# STC12C5A_DIP40_Mini.net
KiCad netlist of a schematic drawn in Altium Designer
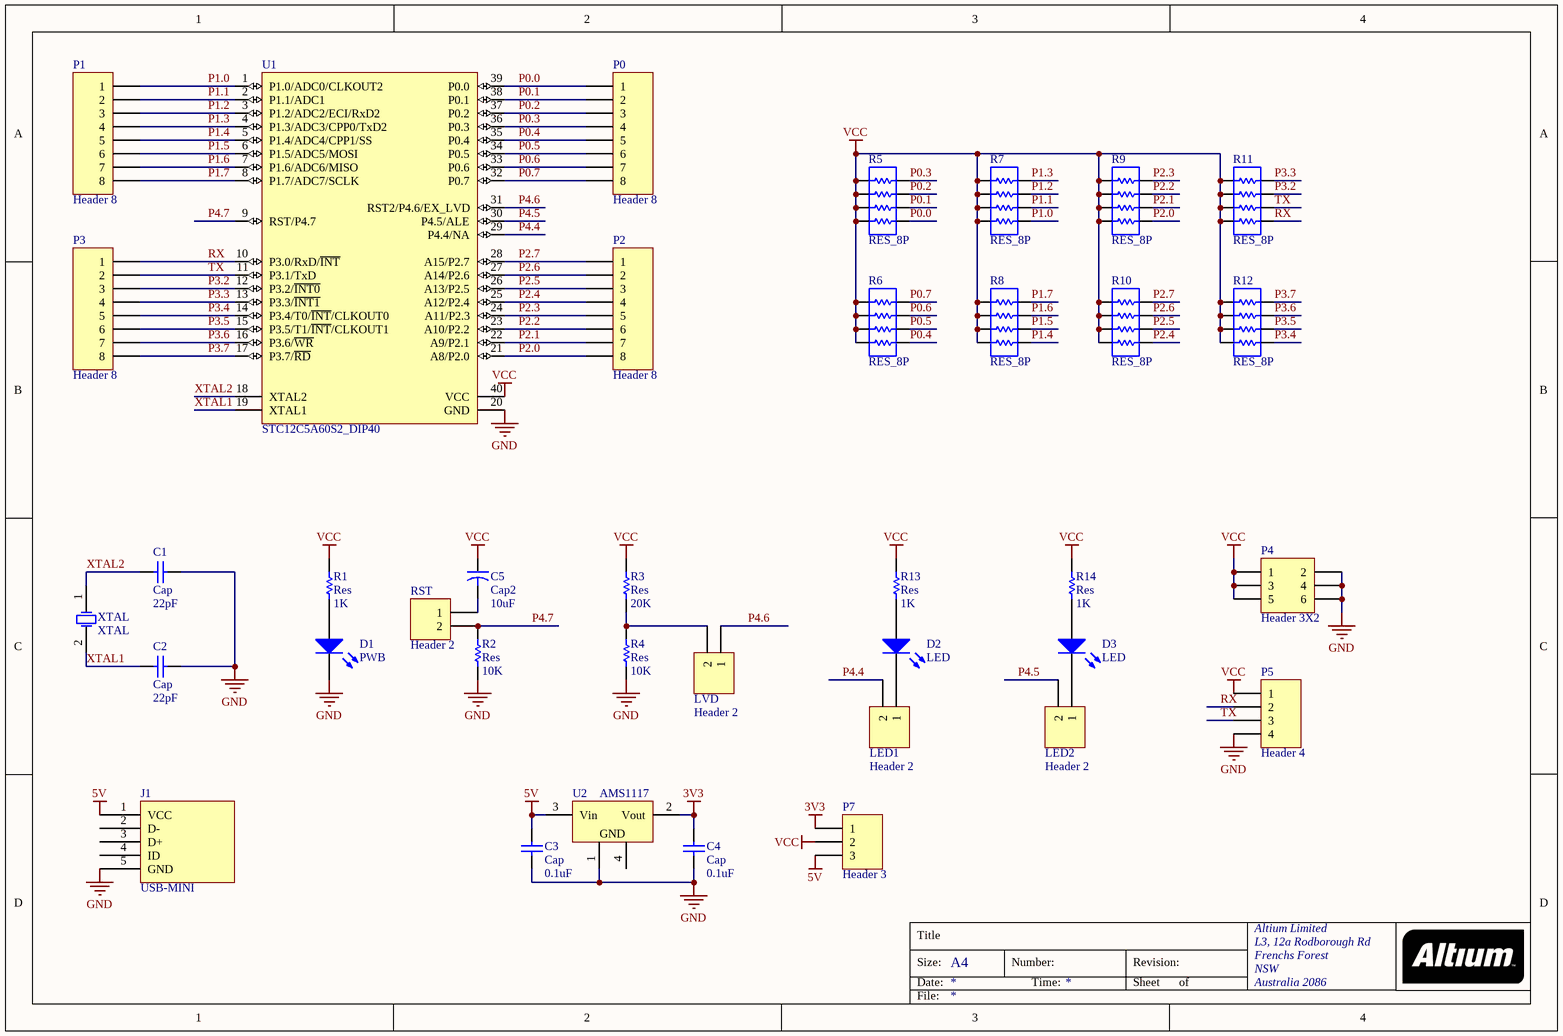
[diagram p0: STC12C5A_DIP40_Mini.SchDoc]

(export (version "E")
  (design (tool "Eeschema 10.0.6"))
  (components
    (comp (ref "C1")
      (value "Cap")
      (footprint "C0805")
      (description "Capacitor")
      (fields (field (name "ALTIUM_VALUE") "22pF") (field (name "PUBLISHER") "Altium Limited"))
      (libsource (lib "Devices") (part "Cap"))
    )
    (comp (ref "C2")
      (value "Cap")
      (footprint "C0805")
      (description "Capacitor")
      (fields (field (name "ALTIUM_VALUE") "22pF") (field (name "PUBLISHER") "Altium Limited"))
      (libsource (lib "Devices") (part "Cap"))
    )
    (comp (ref "C3")
      (value "Cap")
      (footprint "C0805")
      (description "Capacitor")
      (fields (field (name "ALTIUM_VALUE") "0.1uF") (field (name "PUBLISHER") "Altium Limited"))
      (libsource (lib "Devices") (part "Cap"))
    )
    (comp (ref "C4")
      (value "Cap")
      (footprint "C0805")
      (description "Capacitor")
      (fields (field (name "ALTIUM_VALUE") "0.1uF") (field (name "PUBLISHER") "Altium Limited"))
      (libsource (lib "Devices") (part "Cap"))
    )
    (comp (ref "C5")
      (value "Cap2")
      (footprint "C1210")
      (description "Capacitor")
      (fields (field (name "ALTIUM_VALUE") "10uF") (field (name "PUBLISHER") "Altium Limited"))
      (libsource (lib "Devices") (part "Cap2"))
    )
    (comp (ref "D1")
      (value "PWB")
      (footprint "C0805")
      (description "发光二极管")
      (libsource (lib "Devices") (part "LED-2P"))
    )
    (comp (ref "D2")
      (value "LED")
      (footprint "C0805")
      (description "发光二极管")
      (libsource (lib "Devices") (part "LED-2P"))
    )
    (comp (ref "D3")
      (value "LED")
      (footprint "C0805")
      (description "发光二极管")
      (libsource (lib "Devices") (part "LED-2P"))
    )
    (comp (ref "J1")
      (value "USB-MINI")
      (footprint "USB-MINI-B-SM")
      (libsource (lib "Connectors") (part "USB-MINI"))
    )
    (comp (ref "LED1")
      (value "Header 2")
      (footprint "HDR1X2")
      (description "Header, 2-Pin")
      (fields (field (name "PUBLISHER") "Altium Limited"))
      (libsource (lib "Connectors") (part "Header 2"))
    )
    (comp (ref "LED2")
      (value "Header 2")
      (footprint "HDR1X2")
      (description "Header, 2-Pin")
      (fields (field (name "PUBLISHER") "Altium Limited"))
      (libsource (lib "Connectors") (part "Header 2"))
    )
    (comp (ref "LVD")
      (value "Header 2")
      (footprint "HDR1X2")
      (description "Header, 2-Pin")
      (fields (field (name "PUBLISHER") "Altium Limited"))
      (libsource (lib "Connectors") (part "Header 2"))
    )
    (comp (ref "P0")
      (value "Header 8")
      (footprint "HDR1X8")
      (description "Header, 8-Pin")
      (fields (field (name "PUBLISHER") "Altium Limited"))
      (libsource (lib "Connectors") (part "Header 8"))
    )
    (comp (ref "P1")
      (value "Header 8")
      (footprint "HDR1X8")
      (description "Header, 8-Pin")
      (fields (field (name "PUBLISHER") "Altium Limited"))
      (libsource (lib "") (part "Header 8_1"))
    )
    (comp (ref "P2")
      (value "Header 8")
      (footprint "HDR1X8")
      (description "Header, 8-Pin")
      (fields (field (name "PUBLISHER") "Altium Limited"))
      (libsource (lib "Connectors") (part "Header 8"))
    )
    (comp (ref "P3")
      (value "Header 8")
      (footprint "HDR1X8")
      (description "Header, 8-Pin")
      (fields (field (name "PUBLISHER") "Altium Limited"))
      (libsource (lib "") (part "Header 8_1"))
    )
    (comp (ref "P4")
      (value "Header 3X2")
      (footprint "HDR2X3")
      (description "Header, 3-Pin, Dual row")
      (fields (field (name "PUBLISHER") "Altium Limited"))
      (libsource (lib "Connectors") (part "Header 3X2"))
    )
    (comp (ref "P5")
      (value "Header 4")
      (footprint "HDR1X4")
      (description "Header, 4-Pin")
      (fields (field (name "PUBLISHER") "Altium Limited"))
      (libsource (lib "Connectors") (part "Header 4"))
    )
    (comp (ref "P7")
      (value "Header 3")
      (footprint "HDR1X3")
      (description "Header, 3-Pin")
      (fields (field (name "PUBLISHER") "Altium Limited"))
      (libsource (lib "Connectors") (part "Header 3"))
    )
    (comp (ref "R1")
      (value "Res")
      (footprint "0805")
      (description "Resistor")
      (fields (field (name "ALTIUM_VALUE") "1K") (field (name "PUBLISHER") "Altium Limited"))
      (libsource (lib "Devices") (part "Res"))
    )
    (comp (ref "R2")
      (value "Res")
      (footprint "0805")
      (description "Resistor")
      (fields (field (name "ALTIUM_VALUE") "10K") (field (name "PUBLISHER") "Altium Limited"))
      (libsource (lib "Devices") (part "Res"))
    )
    (comp (ref "R3")
      (value "Res")
      (footprint "0805")
      (description "Resistor")
      (fields (field (name "ALTIUM_VALUE") "20K") (field (name "PUBLISHER") "Altium Limited"))
      (libsource (lib "Devices") (part "Res"))
    )
    (comp (ref "R4")
      (value "Res")
      (footprint "0805")
      (description "Resistor")
      (fields (field (name "ALTIUM_VALUE") "10K") (field (name "PUBLISHER") "Altium Limited"))
      (libsource (lib "Devices") (part "Res"))
    )
    (comp (ref "R5")
      (value "RES_8P")
      (footprint "RES_8P_0603")
      (description "贴片排阻")
      (libsource (lib "Devices") (part "RES_8P"))
    )
    (comp (ref "R6")
      (value "RES_8P")
      (footprint "RES_8P_0603")
      (description "贴片排阻")
      (libsource (lib "Devices") (part "RES_8P"))
    )
    (comp (ref "R7")
      (value "RES_8P")
      (footprint "RES_8P_0603")
      (description "贴片排阻")
      (libsource (lib "Devices") (part "RES_8P"))
    )
    (comp (ref "R8")
      (value "RES_8P")
      (footprint "RES_8P_0603")
      (description "贴片排阻")
      (libsource (lib "Devices") (part "RES_8P"))
    )
    (comp (ref "R9")
      (value "RES_8P")
      (footprint "RES_8P_0603")
      (description "贴片排阻")
      (libsource (lib "Devices") (part "RES_8P"))
    )
    (comp (ref "R10")
      (value "RES_8P")
      (footprint "RES_8P_0603")
      (description "贴片排阻")
      (libsource (lib "Devices") (part "RES_8P"))
    )
    (comp (ref "R11")
      (value "RES_8P")
      (footprint "RES_8P_0603")
      (description "贴片排阻")
      (libsource (lib "Devices") (part "RES_8P"))
    )
    (comp (ref "R12")
      (value "RES_8P")
      (footprint "RES_8P_0603")
      (description "贴片排阻")
      (libsource (lib "Devices") (part "RES_8P"))
    )
    (comp (ref "R13")
      (value "Res")
      (footprint "0805")
      (description "Resistor")
      (fields (field (name "ALTIUM_VALUE") "1K") (field (name "PUBLISHER") "Altium Limited"))
      (libsource (lib "Devices") (part "Res"))
    )
    (comp (ref "R14")
      (value "Res")
      (footprint "0805")
      (description "Resistor")
      (fields (field (name "ALTIUM_VALUE") "1K") (field (name "PUBLISHER") "Altium Limited"))
      (libsource (lib "Devices") (part "Res"))
    )
    (comp (ref "RST")
      (value "Header 2")
      (footprint "HDR1X2")
      (description "Header, 2-Pin")
      (fields (field (name "PUBLISHER") "Altium Limited"))
      (libsource (lib "Connectors") (part "Header 2"))
    )
    (comp (ref "U1")
      (value "STC12C5A60S2_DIP40")
      (footprint "DIP40")
      (description "增强型8051单片机")
      (libsource (lib "STC") (part "STC12C5A60S2_DIP40"))
    )
    (comp (ref "U2")
      (value "AMS1117")
      (footprint "SOT-223")
      (description "低压稳压器-1A")
      (libsource (lib "IC") (part "AMS1117"))
    )
    (comp (ref "XTAL")
      (value "XTAL")
      (footprint "XTAL1")
      (description "Crystal Oscillator")
      (fields (field (name "PUBLISHER") "Altium Limited"))
      (libsource (lib "Miscellaneous Devices") (part "XTAL"))
    )
  )
  (nets
    (net (code "1") (name "/P0.0") (class "Default")
      (node (ref "P0") (pin "1") (pinfunction "1_1") (pintype "passive"))
      (node (ref "R5") (pin "8") (pinfunction "8_8") (pintype "passive"))
      (node (ref "U1") (pin "39") (pinfunction "P0.0_39") (pintype "bidirectional"))
    )
    (net (code "2") (name "/P0.1") (class "Default")
      (node (ref "P0") (pin "2") (pinfunction "2_2") (pintype "passive"))
      (node (ref "R5") (pin "6") (pinfunction "6_6") (pintype "passive"))
      (node (ref "U1") (pin "38") (pinfunction "P0.1_38") (pintype "bidirectional"))
    )
    (net (code "3") (name "/P0.2") (class "Default")
      (node (ref "P0") (pin "3") (pinfunction "3_3") (pintype "passive"))
      (node (ref "R5") (pin "4") (pinfunction "4_4") (pintype "passive"))
      (node (ref "U1") (pin "37") (pinfunction "P0.2_37") (pintype "bidirectional"))
    )
    (net (code "4") (name "/P0.3") (class "Default")
      (node (ref "P0") (pin "4") (pinfunction "4_4") (pintype "passive"))
      (node (ref "R5") (pin "2") (pinfunction "2_2") (pintype "passive"))
      (node (ref "U1") (pin "36") (pinfunction "P0.3_36") (pintype "bidirectional"))
    )
    (net (code "5") (name "/P0.4") (class "Default")
      (node (ref "P0") (pin "5") (pinfunction "5_5") (pintype "passive"))
      (node (ref "R6") (pin "8") (pinfunction "8_8") (pintype "passive"))
      (node (ref "U1") (pin "35") (pinfunction "P0.4_35") (pintype "bidirectional"))
    )
    (net (code "6") (name "/P0.5") (class "Default")
      (node (ref "P0") (pin "6") (pinfunction "6_6") (pintype "passive"))
      (node (ref "R6") (pin "6") (pinfunction "6_6") (pintype "passive"))
      (node (ref "U1") (pin "34") (pinfunction "P0.5_34") (pintype "bidirectional"))
    )
    (net (code "7") (name "/P0.6") (class "Default")
      (node (ref "P0") (pin "7") (pinfunction "7_7") (pintype "passive"))
      (node (ref "R6") (pin "4") (pinfunction "4_4") (pintype "passive"))
      (node (ref "U1") (pin "33") (pinfunction "P0.6_33") (pintype "bidirectional"))
    )
    (net (code "8") (name "/P0.7") (class "Default")
      (node (ref "P0") (pin "8") (pinfunction "8_8") (pintype "passive"))
      (node (ref "R6") (pin "2") (pinfunction "2_2") (pintype "passive"))
      (node (ref "U1") (pin "32") (pinfunction "P0.7_32") (pintype "bidirectional"))
    )
    (net (code "9") (name "/P1.0") (class "Default")
      (node (ref "P1") (pin "1") (pinfunction "1_1") (pintype "passive"))
      (node (ref "R7") (pin "8") (pinfunction "8_8") (pintype "passive"))
      (node (ref "U1") (pin "1") (pinfunction "P1.0/ADC0/CLKOUT2_1") (pintype "bidirectional"))
    )
    (net (code "10") (name "/P1.1") (class "Default")
      (node (ref "P1") (pin "2") (pinfunction "2_2") (pintype "passive"))
      (node (ref "R7") (pin "6") (pinfunction "6_6") (pintype "passive"))
      (node (ref "U1") (pin "2") (pinfunction "P1.1/ADC1_2") (pintype "bidirectional"))
    )
    (net (code "11") (name "/P1.2") (class "Default")
      (node (ref "P1") (pin "3") (pinfunction "3_3") (pintype "passive"))
      (node (ref "R7") (pin "4") (pinfunction "4_4") (pintype "passive"))
      (node (ref "U1") (pin "3") (pinfunction "P1.2/ADC2/ECI/RxD2_3") (pintype "bidirectional"))
    )
    (net (code "12") (name "/P1.3") (class "Default")
      (node (ref "P1") (pin "4") (pinfunction "4_4") (pintype "passive"))
      (node (ref "R7") (pin "2") (pinfunction "2_2") (pintype "passive"))
      (node (ref "U1") (pin "4") (pinfunction "P1.3/ADC3/CPP0/TxD2_4") (pintype "bidirectional"))
    )
    (net (code "13") (name "/P1.4") (class "Default")
      (node (ref "P1") (pin "5") (pinfunction "5_5") (pintype "passive"))
      (node (ref "R8") (pin "8") (pinfunction "8_8") (pintype "passive"))
      (node (ref "U1") (pin "5") (pinfunction "P1.4/ADC4/CPP1/SS_5") (pintype "bidirectional"))
    )
    (net (code "14") (name "/P1.5") (class "Default")
      (node (ref "P1") (pin "6") (pinfunction "6_6") (pintype "passive"))
      (node (ref "R8") (pin "6") (pinfunction "6_6") (pintype "passive"))
      (node (ref "U1") (pin "6") (pinfunction "P1.5/ADC5/MOSI_6") (pintype "bidirectional"))
    )
    (net (code "15") (name "/P1.6") (class "Default")
      (node (ref "P1") (pin "7") (pinfunction "7_7") (pintype "passive"))
      (node (ref "R8") (pin "4") (pinfunction "4_4") (pintype "passive"))
      (node (ref "U1") (pin "7") (pinfunction "P1.6/ADC6/MISO_7") (pintype "bidirectional"))
    )
    (net (code "16") (name "/P1.7") (class "Default")
      (node (ref "P1") (pin "8") (pinfunction "8_8") (pintype "passive"))
      (node (ref "R8") (pin "2") (pinfunction "2_2") (pintype "passive"))
      (node (ref "U1") (pin "8") (pinfunction "P1.7/ADC7/SCLK_8") (pintype "bidirectional"))
    )
    (net (code "17") (name "/P2.0") (class "Default")
      (node (ref "P2") (pin "8") (pinfunction "8_8") (pintype "passive"))
      (node (ref "R9") (pin "8") (pinfunction "8_8") (pintype "passive"))
      (node (ref "U1") (pin "21") (pinfunction "A8/P2.0_21") (pintype "bidirectional"))
    )
    (net (code "18") (name "/P2.1") (class "Default")
      (node (ref "P2") (pin "7") (pinfunction "7_7") (pintype "passive"))
      (node (ref "R9") (pin "6") (pinfunction "6_6") (pintype "passive"))
      (node (ref "U1") (pin "22") (pinfunction "A9/P2.1_22") (pintype "bidirectional"))
    )
    (net (code "19") (name "/P2.2") (class "Default")
      (node (ref "P2") (pin "6") (pinfunction "6_6") (pintype "passive"))
      (node (ref "R9") (pin "4") (pinfunction "4_4") (pintype "passive"))
      (node (ref "U1") (pin "23") (pinfunction "A10/P2.2_23") (pintype "bidirectional"))
    )
    (net (code "20") (name "/P2.3") (class "Default")
      (node (ref "P2") (pin "5") (pinfunction "5_5") (pintype "passive"))
      (node (ref "R9") (pin "2") (pinfunction "2_2") (pintype "passive"))
      (node (ref "U1") (pin "24") (pinfunction "A11/P2.3_24") (pintype "bidirectional"))
    )
    (net (code "21") (name "/P2.4") (class "Default")
      (node (ref "P2") (pin "4") (pinfunction "4_4") (pintype "passive"))
      (node (ref "R10") (pin "8") (pinfunction "8_8") (pintype "passive"))
      (node (ref "U1") (pin "25") (pinfunction "A12/P2.4_25") (pintype "bidirectional"))
    )
    (net (code "22") (name "/P2.5") (class "Default")
      (node (ref "P2") (pin "3") (pinfunction "3_3") (pintype "passive"))
      (node (ref "R10") (pin "6") (pinfunction "6_6") (pintype "passive"))
      (node (ref "U1") (pin "26") (pinfunction "A13/P2.5_26") (pintype "bidirectional"))
    )
    (net (code "23") (name "/P2.6") (class "Default")
      (node (ref "P2") (pin "2") (pinfunction "2_2") (pintype "passive"))
      (node (ref "R10") (pin "4") (pinfunction "4_4") (pintype "passive"))
      (node (ref "U1") (pin "27") (pinfunction "A14/P2.6_27") (pintype "bidirectional"))
    )
    (net (code "24") (name "/P2.7") (class "Default")
      (node (ref "P2") (pin "1") (pinfunction "1_1") (pintype "passive"))
      (node (ref "R10") (pin "2") (pinfunction "2_2") (pintype "passive"))
      (node (ref "U1") (pin "28") (pinfunction "A15/P2.7_28") (pintype "bidirectional"))
    )
    (net (code "25") (name "/P3.2") (class "Default")
      (node (ref "P3") (pin "3") (pinfunction "3_3") (pintype "passive"))
      (node (ref "R11") (pin "4") (pinfunction "4_4") (pintype "passive"))
      (node (ref "U1") (pin "12") (pinfunction "P3.2/~{INT0}_12") (pintype "bidirectional"))
    )
    (net (code "26") (name "/P3.3") (class "Default")
      (node (ref "P3") (pin "4") (pinfunction "4_4") (pintype "passive"))
      (node (ref "R11") (pin "2") (pinfunction "2_2") (pintype "passive"))
      (node (ref "U1") (pin "13") (pinfunction "P3.3/~{INT1}_13") (pintype "bidirectional"))
    )
    (net (code "27") (name "/P3.4") (class "Default")
      (node (ref "P3") (pin "5") (pinfunction "5_5") (pintype "passive"))
      (node (ref "R12") (pin "8") (pinfunction "8_8") (pintype "passive"))
      (node (ref "U1") (pin "14") (pinfunction "P3.4/T0/~{INT}/CLKOUT0_14") (pintype "bidirectional"))
    )
    (net (code "28") (name "/P3.5") (class "Default")
      (node (ref "P3") (pin "6") (pinfunction "6_6") (pintype "passive"))
      (node (ref "R12") (pin "6") (pinfunction "6_6") (pintype "passive"))
      (node (ref "U1") (pin "15") (pinfunction "P3.5/T1/~{INT}/CLKOUT1_15") (pintype "bidirectional"))
    )
    (net (code "29") (name "/P3.6") (class "Default")
      (node (ref "P3") (pin "7") (pinfunction "7_7") (pintype "passive"))
      (node (ref "R12") (pin "4") (pinfunction "4_4") (pintype "passive"))
      (node (ref "U1") (pin "16") (pinfunction "P3.6/~{WR}_16") (pintype "bidirectional"))
    )
    (net (code "30") (name "/P3.7") (class "Default")
      (node (ref "P3") (pin "8") (pinfunction "8_8") (pintype "passive"))
      (node (ref "R12") (pin "2") (pinfunction "2_2") (pintype "passive"))
      (node (ref "U1") (pin "17") (pinfunction "P3.7/~{RD}_17") (pintype "bidirectional"))
    )
    (net (code "31") (name "/P4.4") (class "Default")
      (node (ref "LED1") (pin "2") (pinfunction "2_2") (pintype "passive"))
      (node (ref "U1") (pin "29") (pinfunction "P4.4/NA_29") (pintype "bidirectional"))
    )
    (net (code "32") (name "/P4.5") (class "Default")
      (node (ref "LED2") (pin "2") (pinfunction "2_2") (pintype "passive"))
      (node (ref "U1") (pin "30") (pinfunction "P4.5/ALE_30") (pintype "bidirectional"))
    )
    (net (code "33") (name "/P4.6") (class "Default")
      (node (ref "LVD") (pin "1") (pinfunction "1_1") (pintype "passive"))
      (node (ref "U1") (pin "31") (pinfunction "RST2/P4.6/EX_LVD_31") (pintype "bidirectional"))
    )
    (net (code "34") (name "/P4.7") (class "Default")
      (node (ref "R2") (pin "2") (pinfunction "2_2") (pintype "passive"))
      (node (ref "RST") (pin "2") (pinfunction "2_2") (pintype "passive"))
      (node (ref "U1") (pin "9") (pinfunction "RST/P4.7_9") (pintype "bidirectional"))
    )
    (net (code "35") (name "/RX") (class "Default")
      (node (ref "P3") (pin "1") (pinfunction "1_1") (pintype "passive"))
      (node (ref "P5") (pin "2") (pinfunction "2_2") (pintype "passive"))
      (node (ref "R11") (pin "8") (pinfunction "8_8") (pintype "passive"))
      (node (ref "U1") (pin "10") (pinfunction "P3.0/RxD/~{INT}_10") (pintype "bidirectional"))
    )
    (net (code "36") (name "/TX") (class "Default")
      (node (ref "P3") (pin "2") (pinfunction "2_2") (pintype "passive"))
      (node (ref "P5") (pin "3") (pinfunction "3_3") (pintype "passive"))
      (node (ref "R11") (pin "6") (pinfunction "6_6") (pintype "passive"))
      (node (ref "U1") (pin "11") (pinfunction "P3.1/TxD_11") (pintype "bidirectional"))
    )
    (net (code "37") (name "/XTAL1") (class "Default")
      (node (ref "C2") (pin "1") (pinfunction "1_1") (pintype "passive"))
      (node (ref "U1") (pin "19") (pinfunction "XTAL1_19") (pintype "passive"))
      (node (ref "XTAL") (pin "2") (pinfunction "OSC2_2") (pintype "passive"))
    )
    (net (code "38") (name "/XTAL2") (class "Default")
      (node (ref "C1") (pin "1") (pinfunction "1_1") (pintype "passive"))
      (node (ref "U1") (pin "18") (pinfunction "XTAL2_18") (pintype "passive"))
      (node (ref "XTAL") (pin "1") (pinfunction "OSC1_1") (pintype "passive"))
    )
    (net (code "39") (name "3V3") (class "Default")
      (node (ref "C4") (pin "2") (pinfunction "2_2") (pintype "passive"))
      (node (ref "P7") (pin "1") (pinfunction "1_1") (pintype "passive"))
      (node (ref "U2") (pin "2") (pinfunction "Vout_2") (pintype "passive"))
    )
    (net (code "40") (name "5V") (class "Default")
      (node (ref "C3") (pin "2") (pinfunction "2_2") (pintype "passive"))
      (node (ref "J1") (pin "1") (pinfunction "VCC_1") (pintype "power_in"))
      (node (ref "P7") (pin "3") (pinfunction "3_3") (pintype "passive"))
      (node (ref "U2") (pin "3") (pinfunction "Vin_3") (pintype "passive"))
    )
    (net (code "41") (name "GND") (class "Default")
      (node (ref "C1") (pin "2") (pinfunction "2_2") (pintype "passive"))
      (node (ref "C2") (pin "2") (pinfunction "2_2") (pintype "passive"))
      (node (ref "C3") (pin "1") (pinfunction "1_1") (pintype "passive"))
      (node (ref "C4") (pin "1") (pinfunction "1_1") (pintype "passive"))
      (node (ref "D1") (pin "2") (pinfunction "K_2") (pintype "passive"))
      (node (ref "J1") (pin "5") (pinfunction "GND_5") (pintype "power_in"))
      (node (ref "P4") (pin "2") (pinfunction "2_2") (pintype "passive"))
      (node (ref "P4") (pin "4") (pinfunction "4_4") (pintype "passive"))
      (node (ref "P4") (pin "6") (pinfunction "6_6") (pintype "passive"))
      (node (ref "P5") (pin "4") (pinfunction "4_4") (pintype "passive"))
      (node (ref "R2") (pin "1") (pinfunction "1_1") (pintype "passive"))
      (node (ref "R4") (pin "1") (pinfunction "1_1") (pintype "passive"))
      (node (ref "U1") (pin "20") (pinfunction "GND_20") (pintype "power_in"))
      (node (ref "U2") (pin "1") (pinfunction "GND_1") (pintype "passive"))
    )
    (net (code "42") (name "Net-(C5-Pad2)") (class "Default")
      (node (ref "C5") (pin "2") (pinfunction "2_2") (pintype "passive"))
      (node (ref "RST") (pin "1") (pinfunction "1_1") (pintype "passive"))
    )
    (net (code "43") (name "Net-(D1-A)") (class "Default")
      (node (ref "D1") (pin "1") (pinfunction "A_1") (pintype "passive"))
      (node (ref "R1") (pin "1") (pinfunction "1_1") (pintype "passive"))
    )
    (net (code "44") (name "Net-(D2-A)") (class "Default")
      (node (ref "D2") (pin "1") (pinfunction "A_1") (pintype "passive"))
      (node (ref "R13") (pin "1") (pinfunction "1_1") (pintype "passive"))
    )
    (net (code "45") (name "Net-(D2-K)") (class "Default")
      (node (ref "D2") (pin "2") (pinfunction "K_2") (pintype "passive"))
      (node (ref "LED1") (pin "1") (pinfunction "1_1") (pintype "passive"))
    )
    (net (code "46") (name "Net-(D3-A)") (class "Default")
      (node (ref "D3") (pin "1") (pinfunction "A_1") (pintype "passive"))
      (node (ref "R14") (pin "1") (pinfunction "1_1") (pintype "passive"))
    )
    (net (code "47") (name "Net-(D3-K)") (class "Default")
      (node (ref "D3") (pin "2") (pinfunction "K_2") (pintype "passive"))
      (node (ref "LED2") (pin "1") (pinfunction "1_1") (pintype "passive"))
    )
    (net (code "48") (name "Net-(LVD-Pad2)") (class "Default")
      (node (ref "LVD") (pin "2") (pinfunction "2_2") (pintype "passive"))
      (node (ref "R3") (pin "1") (pinfunction "1_1") (pintype "passive"))
      (node (ref "R4") (pin "2") (pinfunction "2_2") (pintype "passive"))
    )
    (net (code "49") (name "VCC") (class "Default")
      (node (ref "C5") (pin "1") (pinfunction "1_1") (pintype "passive"))
      (node (ref "P4") (pin "1") (pinfunction "1_1") (pintype "passive"))
      (node (ref "P4") (pin "3") (pinfunction "3_3") (pintype "passive"))
      (node (ref "P4") (pin "5") (pinfunction "5_5") (pintype "passive"))
      (node (ref "P5") (pin "1") (pinfunction "1_1") (pintype "passive"))
      (node (ref "P7") (pin "2") (pinfunction "2_2") (pintype "passive"))
      (node (ref "R1") (pin "2") (pinfunction "2_2") (pintype "passive"))
      (node (ref "R10") (pin "1") (pinfunction "1_1") (pintype "passive"))
      (node (ref "R10") (pin "3") (pinfunction "3_3") (pintype "passive"))
      (node (ref "R10") (pin "5") (pinfunction "5_5") (pintype "passive"))
      (node (ref "R10") (pin "7") (pinfunction "7_7") (pintype "passive"))
      (node (ref "R11") (pin "1") (pinfunction "1_1") (pintype "passive"))
      (node (ref "R11") (pin "3") (pinfunction "3_3") (pintype "passive"))
      (node (ref "R11") (pin "5") (pinfunction "5_5") (pintype "passive"))
      (node (ref "R11") (pin "7") (pinfunction "7_7") (pintype "passive"))
      (node (ref "R12") (pin "1") (pinfunction "1_1") (pintype "passive"))
      (node (ref "R12") (pin "3") (pinfunction "3_3") (pintype "passive"))
      (node (ref "R12") (pin "5") (pinfunction "5_5") (pintype "passive"))
      (node (ref "R12") (pin "7") (pinfunction "7_7") (pintype "passive"))
      (node (ref "R13") (pin "2") (pinfunction "2_2") (pintype "passive"))
      (node (ref "R14") (pin "2") (pinfunction "2_2") (pintype "passive"))
      (node (ref "R3") (pin "2") (pinfunction "2_2") (pintype "passive"))
      (node (ref "R5") (pin "1") (pinfunction "1_1") (pintype "passive"))
      (node (ref "R5") (pin "3") (pinfunction "3_3") (pintype "passive"))
      (node (ref "R5") (pin "5") (pinfunction "5_5") (pintype "passive"))
      (node (ref "R5") (pin "7") (pinfunction "7_7") (pintype "passive"))
      (node (ref "R6") (pin "1") (pinfunction "1_1") (pintype "passive"))
      (node (ref "R6") (pin "3") (pinfunction "3_3") (pintype "passive"))
      (node (ref "R6") (pin "5") (pinfunction "5_5") (pintype "passive"))
      (node (ref "R6") (pin "7") (pinfunction "7_7") (pintype "passive"))
      (node (ref "R7") (pin "1") (pinfunction "1_1") (pintype "passive"))
      (node (ref "R7") (pin "3") (pinfunction "3_3") (pintype "passive"))
      (node (ref "R7") (pin "5") (pinfunction "5_5") (pintype "passive"))
      (node (ref "R7") (pin "7") (pinfunction "7_7") (pintype "passive"))
      (node (ref "R8") (pin "1") (pinfunction "1_1") (pintype "passive"))
      (node (ref "R8") (pin "3") (pinfunction "3_3") (pintype "passive"))
      (node (ref "R8") (pin "5") (pinfunction "5_5") (pintype "passive"))
      (node (ref "R8") (pin "7") (pinfunction "7_7") (pintype "passive"))
      (node (ref "R9") (pin "1") (pinfunction "1_1") (pintype "passive"))
      (node (ref "R9") (pin "3") (pinfunction "3_3") (pintype "passive"))
      (node (ref "R9") (pin "5") (pinfunction "5_5") (pintype "passive"))
      (node (ref "R9") (pin "7") (pinfunction "7_7") (pintype "passive"))
      (node (ref "U1") (pin "40") (pinfunction "VCC_40") (pintype "power_in"))
    )
    (net (code "50") (name "unconnected-(J1-D+-Pad3)") (class "Default")
      (node (ref "J1") (pin "3") (pinfunction "D+_3") (pintype "passive"))
    )
    (net (code "51") (name "unconnected-(J1-D--Pad2)") (class "Default")
      (node (ref "J1") (pin "2") (pinfunction "D-_2") (pintype "passive"))
    )
    (net (code "52") (name "unconnected-(J1-ID-Pad4)") (class "Default")
      (node (ref "J1") (pin "4") (pinfunction "ID_4") (pintype "passive"))
    )
    (net (code "53") (name "unconnected-(U2-GND-Pad4)") (class "Default")
      (node (ref "U2") (pin "4") (pinfunction "GND_4") (pintype "passive"))
    )
  )
)
